# 18_I2S.net
KiCad netlist of a schematic drawn in Altium Designer
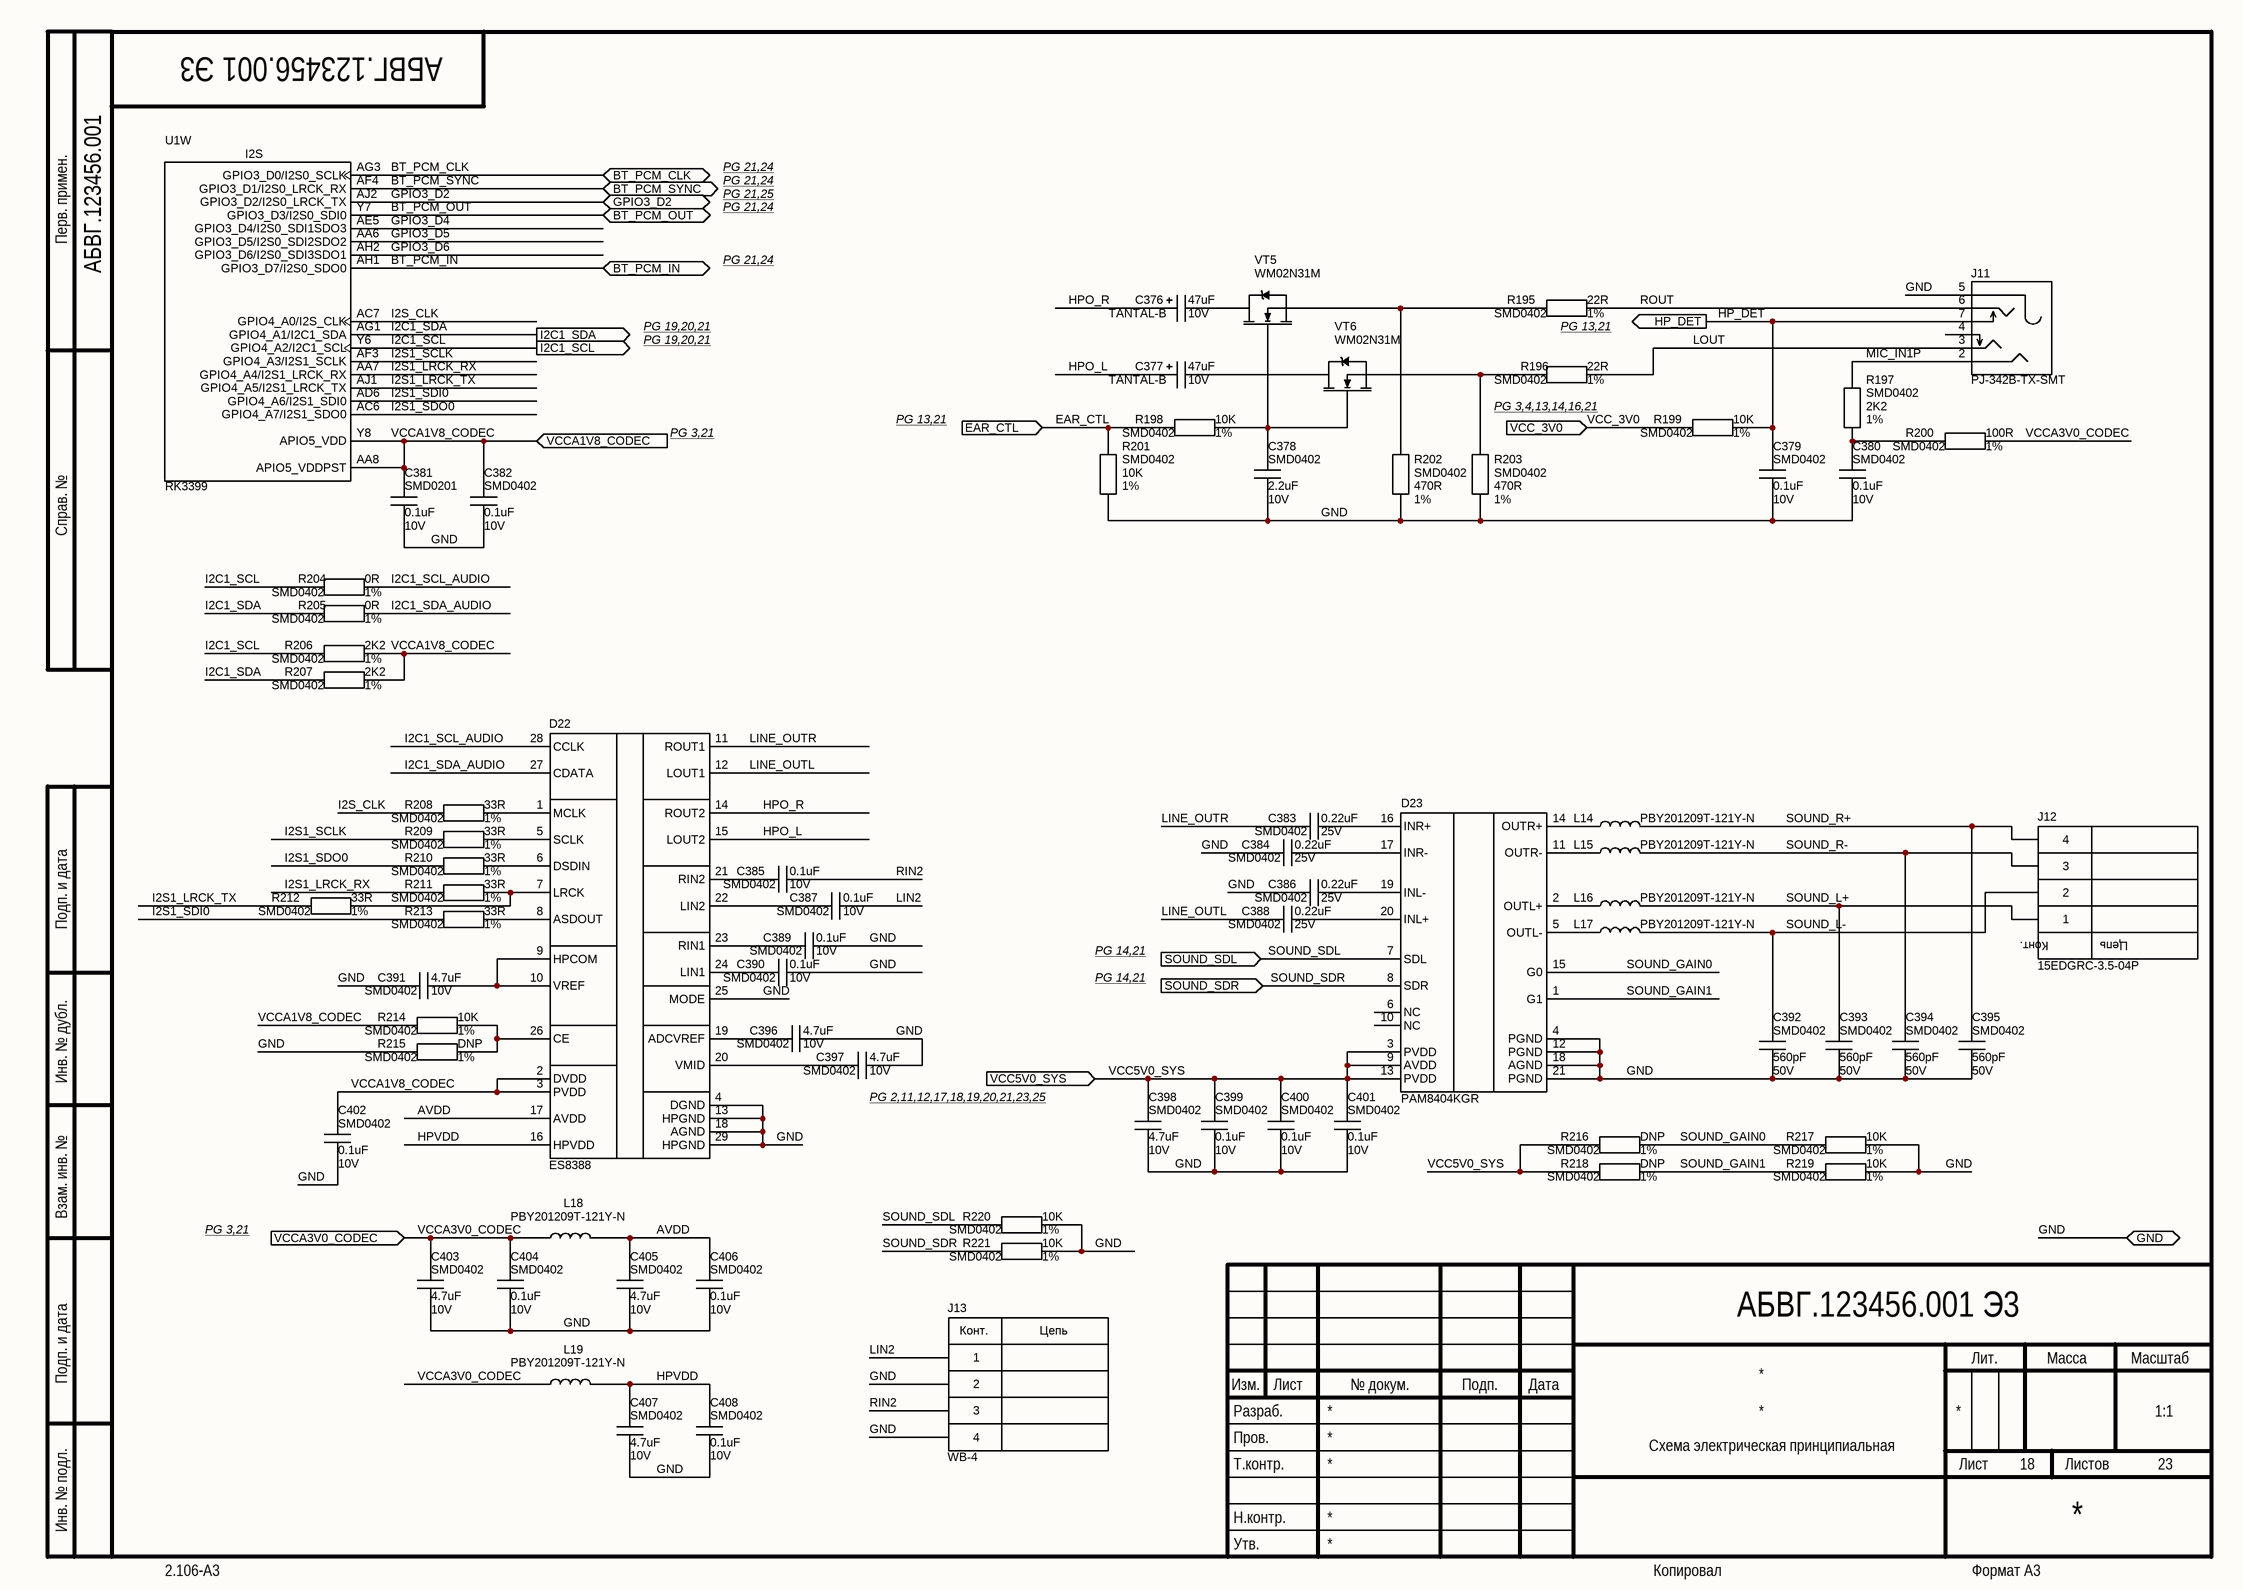
[diagram p0: 18 I2S.SchDoc]

(export (version "E")
  (design (tool "Eeschema 10.0.6"))
  (components
    (comp (ref "C376")
      (value "47uF")
      (footprint "TANTAL-B")
      (fields
        (field (name "PARTNUMBER") "CA45L-B010K476TE500")
        (field (name "TOLERANCE") "20%")
        (field (name "PACKAGE") "TANTAL-B")
        (field (name "VOLTAGE") "10V")
      )
      (libsource (lib "Didur_SchLib_1") (part "Tantal"))
    )
    (comp (ref "C377")
      (value "47uF")
      (footprint "TANTAL-B")
      (fields
        (field (name "PARTNUMBER") "CA45L-B010K476TE500")
        (field (name "TOLERANCE") "20%")
        (field (name "PACKAGE") "TANTAL-B")
        (field (name "VOLTAGE") "10V")
      )
      (libsource (lib "Didur_SchLib_1") (part "Tantal"))
    )
    (comp (ref "C378")
      (value "2.2uF")
      (footprint "Didur_PcbLib_1:CAP_SMD_0402")
      (fields
        (field (name "PACKAGE") "SMD0402")
        (field (name "PARTNUMBER") "CC0402KRX5R6BB225")
        (field (name "VOLTAGE") "10V")
      )
      (libsource (lib "Didur_SchLib_1") (part "Ceramic_Cap"))
    )
    (comp (ref "C379")
      (value "0.1uF")
      (footprint "Didur_PcbLib_1:CAP_SMD_0402")
      (fields
        (field (name "PACKAGE") "SMD0402")
        (field (name "PARTNUMBER") "CC0402KRX5R6BB104")
        (field (name "VOLTAGE") "10V")
      )
      (libsource (lib "Didur_SchLib_1") (part "Ceramic_Cap"))
    )
    (comp (ref "C380")
      (value "0.1uF")
      (footprint "Didur_PcbLib_1:CAP_SMD_0402")
      (fields
        (field (name "PACKAGE") "SMD0402")
        (field (name "PARTNUMBER") "CC0402KRX5R6BB104")
        (field (name "VOLTAGE") "10V")
      )
      (libsource (lib "Didur_SchLib_1") (part "Ceramic_Cap"))
    )
    (comp (ref "C381")
      (value "0.1uF")
      (footprint "Didur_PcbLib_1:CAP_SMD_0201")
      (fields
        (field (name "PACKAGE") "SMD0201")
        (field (name "PARTNUMBER") "CC0201KRX5R6BB104")
        (field (name "VOLTAGE") "10V")
      )
      (libsource (lib "Didur_SchLib_1") (part "Ceramic_Cap"))
    )
    (comp (ref "C382")
      (value "0.1uF")
      (footprint "Didur_PcbLib_1:CAP_SMD_0402")
      (fields
        (field (name "PACKAGE") "SMD0402")
        (field (name "PARTNUMBER") "CC0402KRX5R6BB104")
        (field (name "VOLTAGE") "10V")
      )
      (libsource (lib "Didur_SchLib_1") (part "Ceramic_Cap"))
    )
    (comp (ref "C383")
      (value "0.22uF")
      (footprint "Didur_PcbLib_1:CAP_SMD_0402")
      (fields
        (field (name "PACKAGE") "SMD0402")
        (field (name "PARTNUMBER") "CC0402KRX5R8BB224")
        (field (name "VOLTAGE") "25V")
      )
      (libsource (lib "Didur_SchLib_1") (part "Ceramic_Cap"))
    )
    (comp (ref "C384")
      (value "0.22uF")
      (footprint "Didur_PcbLib_1:CAP_SMD_0402")
      (fields
        (field (name "PACKAGE") "SMD0402")
        (field (name "PARTNUMBER") "CC0402KRX5R8BB224")
        (field (name "VOLTAGE") "25V")
      )
      (libsource (lib "Didur_SchLib_1") (part "Ceramic_Cap"))
    )
    (comp (ref "C385")
      (value "0.1uF")
      (footprint "Didur_PcbLib_1:CAP_SMD_0402")
      (fields
        (field (name "PACKAGE") "SMD0402")
        (field (name "PARTNUMBER") "CC0402KRX5R6BB104")
        (field (name "VOLTAGE") "10V")
      )
      (libsource (lib "Didur_SchLib_1") (part "Ceramic_Cap"))
    )
    (comp (ref "C386")
      (value "0.22uF")
      (footprint "Didur_PcbLib_1:CAP_SMD_0402")
      (fields
        (field (name "PACKAGE") "SMD0402")
        (field (name "PARTNUMBER") "CC0402KRX5R8BB224")
        (field (name "VOLTAGE") "25V")
      )
      (libsource (lib "Didur_SchLib_1") (part "Ceramic_Cap"))
    )
    (comp (ref "C387")
      (value "0.1uF")
      (footprint "Didur_PcbLib_1:CAP_SMD_0402")
      (fields
        (field (name "PACKAGE") "SMD0402")
        (field (name "PARTNUMBER") "CC0402KRX5R6BB104")
        (field (name "VOLTAGE") "10V")
      )
      (libsource (lib "Didur_SchLib_1") (part "Ceramic_Cap"))
    )
    (comp (ref "C388")
      (value "0.22uF")
      (footprint "Didur_PcbLib_1:CAP_SMD_0402")
      (fields
        (field (name "PACKAGE") "SMD0402")
        (field (name "PARTNUMBER") "CC0402KRX5R8BB224")
        (field (name "VOLTAGE") "25V")
      )
      (libsource (lib "Didur_SchLib_1") (part "Ceramic_Cap"))
    )
    (comp (ref "C389")
      (value "0.1uF")
      (footprint "Didur_PcbLib_1:CAP_SMD_0402")
      (fields
        (field (name "PACKAGE") "SMD0402")
        (field (name "PARTNUMBER") "CC0402KRX5R6BB104")
        (field (name "VOLTAGE") "10V")
      )
      (libsource (lib "Didur_SchLib_1") (part "Ceramic_Cap"))
    )
    (comp (ref "C390")
      (value "0.1uF")
      (footprint "Didur_PcbLib_1:CAP_SMD_0402")
      (fields
        (field (name "PACKAGE") "SMD0402")
        (field (name "PARTNUMBER") "CC0402KRX5R6BB104")
        (field (name "VOLTAGE") "10V")
      )
      (libsource (lib "Didur_SchLib_1") (part "Ceramic_Cap"))
    )
    (comp (ref "C391")
      (value "4.7uF")
      (footprint "Didur_PcbLib_1:CAP_SMD_0402")
      (fields
        (field (name "PACKAGE") "SMD0402")
        (field (name "PARTNUMBER") "CL05A475KP5NRNC")
        (field (name "VOLTAGE") "10V")
      )
      (libsource (lib "Didur_SchLib_1") (part "Ceramic_Cap"))
    )
    (comp (ref "C392")
      (value "560pF")
      (footprint "Didur_PcbLib_1:CAP_SMD_0402")
      (fields
        (field (name "PACKAGE") "SMD0402")
        (field (name "PARTNUMBER") "CC0402JRX7R9BB561")
        (field (name "VOLTAGE") "50V")
      )
      (libsource (lib "Didur_SchLib_1") (part "Ceramic_Cap"))
    )
    (comp (ref "C393")
      (value "560pF")
      (footprint "Didur_PcbLib_1:CAP_SMD_0402")
      (fields
        (field (name "PACKAGE") "SMD0402")
        (field (name "PARTNUMBER") "CC0402JRX7R9BB561")
        (field (name "VOLTAGE") "50V")
      )
      (libsource (lib "Didur_SchLib_1") (part "Ceramic_Cap"))
    )
    (comp (ref "C394")
      (value "560pF")
      (footprint "Didur_PcbLib_1:CAP_SMD_0402")
      (fields
        (field (name "PACKAGE") "SMD0402")
        (field (name "PARTNUMBER") "CC0402JRX7R9BB561")
        (field (name "VOLTAGE") "50V")
      )
      (libsource (lib "Didur_SchLib_1") (part "Ceramic_Cap"))
    )
    (comp (ref "C395")
      (value "560pF")
      (footprint "Didur_PcbLib_1:CAP_SMD_0402")
      (fields
        (field (name "PACKAGE") "SMD0402")
        (field (name "PARTNUMBER") "CC0402JRX7R9BB561")
        (field (name "VOLTAGE") "50V")
      )
      (libsource (lib "Didur_SchLib_1") (part "Ceramic_Cap"))
    )
    (comp (ref "C396")
      (value "4.7uF")
      (footprint "Didur_PcbLib_1:CAP_SMD_0402")
      (fields
        (field (name "PACKAGE") "SMD0402")
        (field (name "PARTNUMBER") "CL05A475KP5NRNC")
        (field (name "VOLTAGE") "10V")
      )
      (libsource (lib "Didur_SchLib_1") (part "Ceramic_Cap"))
    )
    (comp (ref "C397")
      (value "4.7uF")
      (footprint "Didur_PcbLib_1:CAP_SMD_0402")
      (fields
        (field (name "PACKAGE") "SMD0402")
        (field (name "PARTNUMBER") "CL05A475KP5NRNC")
        (field (name "VOLTAGE") "10V")
      )
      (libsource (lib "Didur_SchLib_1") (part "Ceramic_Cap"))
    )
    (comp (ref "C398")
      (value "4.7uF")
      (footprint "Didur_PcbLib_1:CAP_SMD_0402")
      (fields
        (field (name "PACKAGE") "SMD0402")
        (field (name "PARTNUMBER") "CL05A475KP5NRNC")
        (field (name "VOLTAGE") "10V")
      )
      (libsource (lib "Didur_SchLib_1") (part "Ceramic_Cap"))
    )
    (comp (ref "C399")
      (value "0.1uF")
      (footprint "Didur_PcbLib_1:CAP_SMD_0402")
      (fields
        (field (name "PACKAGE") "SMD0402")
        (field (name "PARTNUMBER") "CC0402KRX5R6BB104")
        (field (name "VOLTAGE") "10V")
      )
      (libsource (lib "Didur_SchLib_1") (part "Ceramic_Cap"))
    )
    (comp (ref "C400")
      (value "0.1uF")
      (footprint "Didur_PcbLib_1:CAP_SMD_0402")
      (fields
        (field (name "PACKAGE") "SMD0402")
        (field (name "PARTNUMBER") "CC0402KRX5R6BB104")
        (field (name "VOLTAGE") "10V")
      )
      (libsource (lib "Didur_SchLib_1") (part "Ceramic_Cap"))
    )
    (comp (ref "C401")
      (value "0.1uF")
      (footprint "Didur_PcbLib_1:CAP_SMD_0402")
      (fields
        (field (name "PACKAGE") "SMD0402")
        (field (name "PARTNUMBER") "CC0402KRX5R6BB104")
        (field (name "VOLTAGE") "10V")
      )
      (libsource (lib "Didur_SchLib_1") (part "Ceramic_Cap"))
    )
    (comp (ref "C402")
      (value "0.1uF")
      (footprint "Didur_PcbLib_1:CAP_SMD_0402")
      (fields
        (field (name "PACKAGE") "SMD0402")
        (field (name "PARTNUMBER") "CC0402KRX5R6BB104")
        (field (name "VOLTAGE") "10V")
      )
      (libsource (lib "Didur_SchLib_1") (part "Ceramic_Cap"))
    )
    (comp (ref "C403")
      (value "4.7uF")
      (footprint "Didur_PcbLib_1:CAP_SMD_0402")
      (fields
        (field (name "PACKAGE") "SMD0402")
        (field (name "PARTNUMBER") "CL05A475KP5NRNC")
        (field (name "VOLTAGE") "10V")
      )
      (libsource (lib "Didur_SchLib_1") (part "Ceramic_Cap"))
    )
    (comp (ref "C404")
      (value "0.1uF")
      (footprint "Didur_PcbLib_1:CAP_SMD_0402")
      (fields
        (field (name "PACKAGE") "SMD0402")
        (field (name "PARTNUMBER") "CC0402KRX5R6BB104")
        (field (name "VOLTAGE") "10V")
      )
      (libsource (lib "Didur_SchLib_1") (part "Ceramic_Cap"))
    )
    (comp (ref "C405")
      (value "4.7uF")
      (footprint "Didur_PcbLib_1:CAP_SMD_0402")
      (fields
        (field (name "PACKAGE") "SMD0402")
        (field (name "PARTNUMBER") "CL05A475KP5NRNC")
        (field (name "VOLTAGE") "10V")
      )
      (libsource (lib "Didur_SchLib_1") (part "Ceramic_Cap"))
    )
    (comp (ref "C406")
      (value "0.1uF")
      (footprint "Didur_PcbLib_1:CAP_SMD_0402")
      (fields
        (field (name "PACKAGE") "SMD0402")
        (field (name "PARTNUMBER") "CC0402KRX5R6BB104")
        (field (name "VOLTAGE") "10V")
      )
      (libsource (lib "Didur_SchLib_1") (part "Ceramic_Cap"))
    )
    (comp (ref "C407")
      (value "4.7uF")
      (footprint "Didur_PcbLib_1:CAP_SMD_0402")
      (fields
        (field (name "PACKAGE") "SMD0402")
        (field (name "PARTNUMBER") "CL05A475KP5NRNC")
        (field (name "VOLTAGE") "10V")
      )
      (libsource (lib "Didur_SchLib_1") (part "Ceramic_Cap"))
    )
    (comp (ref "C408")
      (value "0.1uF")
      (footprint "Didur_PcbLib_1:CAP_SMD_0402")
      (fields
        (field (name "PACKAGE") "SMD0402")
        (field (name "PARTNUMBER") "CC0402KRX5R6BB104")
        (field (name "VOLTAGE") "10V")
      )
      (libsource (lib "Didur_SchLib_1") (part "Ceramic_Cap"))
    )
    (comp (ref "D22")
      (value "ES8388")
      (footprint "Didur_PcbLib_1:QFN-28 4mmx4mm")
      (libsource (lib "Didur_SchLib_1") (part "ES8388"))
    )
    (comp (ref "D23")
      (value "PAM8404KGR")
      (footprint "Didur_PcbLib_1:QFN-20 4mmx4mm")
      (libsource (lib "Didur_SchLib_1") (part "PAM8404KGR"))
    )
    (comp (ref "J11")
      (value "PJ-342B-TX-SMT")
      (footprint "Didur_PcbLib_1:PJ-342B-TX-SMT")
      (libsource (lib "Didur_SchLib_1") (part "PJ-342B-TX-SMT"))
    )
    (comp (ref "J12")
      (value "15EDGRC-3.5-04P")
      (footprint "Didur_PcbLib_1:15EDGRC-3.5-04P")
      (libsource (lib "") (part "CON4_1"))
    )
    (comp (ref "J13")
      (value "WB-4")
      (footprint "Didur_PcbLib_1:WB-4")
      (fields (field (name "PARTNUMBER") "DS1066-04M(MW-4M)"))
      (libsource (lib "Didur_SchLib_1") (part "CON4"))
    )
    (comp (ref "L14")
      (value "PBY201209T-121Y-N")
      (footprint "Didur_PcbLib_1:IND_SMD_0805")
      (fields (field (name "Comment") "Value"))
      (libsource (lib "Didur_SchLib_1") (part "Inductor_smal"))
    )
    (comp (ref "L15")
      (value "PBY201209T-121Y-N")
      (footprint "Didur_PcbLib_1:IND_SMD_0805")
      (fields (field (name "Comment") "Value"))
      (libsource (lib "Didur_SchLib_1") (part "Inductor_smal"))
    )
    (comp (ref "L16")
      (value "PBY201209T-121Y-N")
      (footprint "Didur_PcbLib_1:IND_SMD_0805")
      (fields (field (name "Comment") "Value"))
      (libsource (lib "Didur_SchLib_1") (part "Inductor_smal"))
    )
    (comp (ref "L17")
      (value "PBY201209T-121Y-N")
      (footprint "Didur_PcbLib_1:IND_SMD_0805")
      (fields (field (name "Comment") "Value"))
      (libsource (lib "Didur_SchLib_1") (part "Inductor_smal"))
    )
    (comp (ref "L18")
      (value "PBY201209T-121Y-N")
      (footprint "Didur_PcbLib_1:IND_SMD_0805")
      (fields (field (name "Comment") "Value"))
      (libsource (lib "Didur_SchLib_1") (part "Inductor_smal"))
    )
    (comp (ref "L19")
      (value "PBY201209T-121Y-N")
      (footprint "Didur_PcbLib_1:IND_SMD_0805")
      (fields (field (name "Comment") "Value"))
      (libsource (lib "Didur_SchLib_1") (part "Inductor_smal"))
    )
    (comp (ref "R195")
      (value "22R")
      (footprint "Didur_PcbLib_1:RES_SMD_0402")
      (fields
        (field (name "PACKAGE") "SMD0402")
        (field (name "PARTNUMBER") "RC0402FR-0722RL")
        (field (name "TOLERANCE") "1%")
      )
      (libsource (lib "") (part "Chip_Res_3"))
    )
    (comp (ref "R196")
      (value "22R")
      (footprint "Didur_PcbLib_1:RES_SMD_0402")
      (fields
        (field (name "PACKAGE") "SMD0402")
        (field (name "PARTNUMBER") "RC0402FR-0722RL")
        (field (name "TOLERANCE") "1%")
      )
      (libsource (lib "") (part "Chip_Res_3"))
    )
    (comp (ref "R197")
      (value "2K2")
      (footprint "Didur_PcbLib_1:RES_SMD_0402")
      (fields
        (field (name "PACKAGE") "SMD0402")
        (field (name "PARTNUMBER") "RC0402FR-072K2L")
        (field (name "TOLERANCE") "1%")
      )
      (libsource (lib "Didur_SchLib_1") (part "Chip_Res"))
    )
    (comp (ref "R198")
      (value "10K")
      (footprint "Didur_PcbLib_1:RES_SMD_0402")
      (fields
        (field (name "PACKAGE") "SMD0402")
        (field (name "PARTNUMBER") "RC0402FR-0710KL")
        (field (name "TOLERANCE") "1%")
      )
      (libsource (lib "") (part "Chip_Res_1"))
    )
    (comp (ref "R199")
      (value "10K")
      (footprint "Didur_PcbLib_1:RES_SMD_0402")
      (fields
        (field (name "PACKAGE") "SMD0402")
        (field (name "PARTNUMBER") "RC0402FR-0710KL")
        (field (name "TOLERANCE") "1%")
      )
      (libsource (lib "") (part "Chip_Res_1"))
    )
    (comp (ref "R200")
      (value "100R")
      (footprint "Didur_PcbLib_1:RES_SMD_0402")
      (fields
        (field (name "PACKAGE") "SMD0402")
        (field (name "PARTNUMBER") "RC0402FR-07100RL")
        (field (name "TOLERANCE") "1%")
      )
      (libsource (lib "Didur_SchLib_1") (part "Chip_Res"))
    )
    (comp (ref "R201")
      (value "10K")
      (footprint "Didur_PcbLib_1:RES_SMD_0402")
      (fields
        (field (name "PACKAGE") "SMD0402")
        (field (name "PARTNUMBER") "RC0402FR-0710KL")
        (field (name "TOLERANCE") "1%")
      )
      (libsource (lib "") (part "Chip_Res_3"))
    )
    (comp (ref "R202")
      (value "470R")
      (footprint "Didur_PcbLib_1:RES_SMD_0402")
      (fields
        (field (name "PACKAGE") "SMD0402")
        (field (name "PARTNUMBER") "RC0402FR-07470RL")
        (field (name "TOLERANCE") "1%")
      )
      (libsource (lib "Didur_SchLib_1") (part "Chip_Res"))
    )
    (comp (ref "R203")
      (value "470R")
      (footprint "Didur_PcbLib_1:RES_SMD_0402")
      (fields
        (field (name "PACKAGE") "SMD0402")
        (field (name "PARTNUMBER") "RC0402FR-07470RL")
        (field (name "TOLERANCE") "1%")
      )
      (libsource (lib "Didur_SchLib_1") (part "Chip_Res"))
    )
    (comp (ref "R204")
      (value "0R")
      (footprint "Didur_PcbLib_1:RES_SMD_0402")
      (fields
        (field (name "PACKAGE") "SMD0402")
        (field (name "PARTNUMBER") "RC0402FR-070RL")
        (field (name "TOLERANCE") "1%")
      )
      (libsource (lib "Didur_SchLib_1") (part "Chip_Res"))
    )
    (comp (ref "R205")
      (value "0R")
      (footprint "Didur_PcbLib_1:RES_SMD_0402")
      (fields
        (field (name "PACKAGE") "SMD0402")
        (field (name "PARTNUMBER") "RC0402FR-070RL")
        (field (name "TOLERANCE") "1%")
      )
      (libsource (lib "Didur_SchLib_1") (part "Chip_Res"))
    )
    (comp (ref "R206")
      (value "2K2")
      (footprint "Didur_PcbLib_1:RES_SMD_0402")
      (fields
        (field (name "PACKAGE") "SMD0402")
        (field (name "PARTNUMBER") "RC0402FR-072K2L")
        (field (name "TOLERANCE") "1%")
      )
      (libsource (lib "") (part "Chip_Res_3"))
    )
    (comp (ref "R207")
      (value "2K2")
      (footprint "Didur_PcbLib_1:RES_SMD_0402")
      (fields
        (field (name "PACKAGE") "SMD0402")
        (field (name "PARTNUMBER") "RC0402FR-072K2L")
        (field (name "TOLERANCE") "1%")
      )
      (libsource (lib "") (part "Chip_Res_3"))
    )
    (comp (ref "R208")
      (value "33R")
      (footprint "Didur_PcbLib_1:RES_SMD_0402")
      (fields
        (field (name "PACKAGE") "SMD0402")
        (field (name "PARTNUMBER") "RC0402FR-0733RL")
        (field (name "TOLERANCE") "1%")
      )
      (libsource (lib "") (part "Chip_Res_2"))
    )
    (comp (ref "R209")
      (value "33R")
      (footprint "Didur_PcbLib_1:RES_SMD_0402")
      (fields
        (field (name "PACKAGE") "SMD0402")
        (field (name "PARTNUMBER") "RC0402FR-0733RL")
        (field (name "TOLERANCE") "1%")
      )
      (libsource (lib "") (part "Chip_Res_2"))
    )
    (comp (ref "R210")
      (value "33R")
      (footprint "Didur_PcbLib_1:RES_SMD_0402")
      (fields
        (field (name "PACKAGE") "SMD0402")
        (field (name "PARTNUMBER") "RC0402FR-0733RL")
        (field (name "TOLERANCE") "1%")
      )
      (libsource (lib "") (part "Chip_Res_2"))
    )
    (comp (ref "R211")
      (value "33R")
      (footprint "Didur_PcbLib_1:RES_SMD_0402")
      (fields
        (field (name "PACKAGE") "SMD0402")
        (field (name "PARTNUMBER") "RC0402FR-0733RL")
        (field (name "TOLERANCE") "1%")
      )
      (libsource (lib "") (part "Chip_Res_2"))
    )
    (comp (ref "R212")
      (value "33R")
      (footprint "Didur_PcbLib_1:RES_SMD_0402")
      (fields
        (field (name "PACKAGE") "SMD0402")
        (field (name "PARTNUMBER") "RC0402FR-0733RL")
        (field (name "TOLERANCE") "1%")
      )
      (libsource (lib "") (part "Chip_Res_2"))
    )
    (comp (ref "R213")
      (value "33R")
      (footprint "Didur_PcbLib_1:RES_SMD_0402")
      (fields
        (field (name "PACKAGE") "SMD0402")
        (field (name "PARTNUMBER") "RC0402FR-0733RL")
        (field (name "TOLERANCE") "1%")
      )
      (libsource (lib "") (part "Chip_Res_2"))
    )
    (comp (ref "R214")
      (value "10K")
      (footprint "Didur_PcbLib_1:RES_SMD_0402")
      (fields
        (field (name "PACKAGE") "SMD0402")
        (field (name "PARTNUMBER") "RC0402FR-0710KL")
        (field (name "TOLERANCE") "1%")
      )
      (libsource (lib "") (part "Chip_Res_1"))
    )
    (comp (ref "R215")
      (value "DNP")
      (footprint "Didur_PcbLib_1:RES_SMD_0402")
      (fields
        (field (name "PACKAGE") "SMD0402")
        (field (name "PARTNUMBER") "Do Not Place")
        (field (name "TOLERANCE") "1%")
      )
      (libsource (lib "Didur_SchLib_1") (part "Chip_Res"))
    )
    (comp (ref "R216")
      (value "DNP")
      (footprint "Didur_PcbLib_1:RES_SMD_0402")
      (fields
        (field (name "PACKAGE") "SMD0402")
        (field (name "PARTNUMBER") "Do Not Place")
        (field (name "TOLERANCE") "1%")
      )
      (libsource (lib "Didur_SchLib_1") (part "Chip_Res"))
    )
    (comp (ref "R217")
      (value "10K")
      (footprint "Didur_PcbLib_1:RES_SMD_0402")
      (fields
        (field (name "PACKAGE") "SMD0402")
        (field (name "PARTNUMBER") "RC0402FR-0710KL")
        (field (name "TOLERANCE") "1%")
      )
      (libsource (lib "") (part "Chip_Res_1"))
    )
    (comp (ref "R218")
      (value "DNP")
      (footprint "Didur_PcbLib_1:RES_SMD_0402")
      (fields
        (field (name "PACKAGE") "SMD0402")
        (field (name "PARTNUMBER") "Do Not Place")
        (field (name "TOLERANCE") "1%")
      )
      (libsource (lib "Didur_SchLib_1") (part "Chip_Res"))
    )
    (comp (ref "R219")
      (value "10K")
      (footprint "Didur_PcbLib_1:RES_SMD_0402")
      (fields
        (field (name "PACKAGE") "SMD0402")
        (field (name "PARTNUMBER") "RC0402FR-0710KL")
        (field (name "TOLERANCE") "1%")
      )
      (libsource (lib "") (part "Chip_Res_1"))
    )
    (comp (ref "R220")
      (value "10K")
      (footprint "Didur_PcbLib_1:RES_SMD_0402")
      (fields
        (field (name "PACKAGE") "SMD0402")
        (field (name "PARTNUMBER") "RC0402FR-0710KL")
        (field (name "TOLERANCE") "1%")
      )
      (libsource (lib "") (part "Chip_Res_1"))
    )
    (comp (ref "R221")
      (value "10K")
      (footprint "Didur_PcbLib_1:RES_SMD_0402")
      (fields
        (field (name "PACKAGE") "SMD0402")
        (field (name "PARTNUMBER") "RC0402FR-0710KL")
        (field (name "TOLERANCE") "1%")
      )
      (libsource (lib "") (part "Chip_Res_1"))
    )
    (comp (ref "U1")
      (value "RK3399")
      (footprint "BGA828C65P31X31_2100X2100X161N")
      (fields (field (name "Comment") "RK3399_FF"))
      (libsource (lib "Didur_SchLib_1") (part "RK3399_FF"))
    )
    (comp (ref "VT5")
      (value "WM02N31M")
      (footprint "SOT23")
      (fields (field (name "Comment") "Value"))
      (libsource (lib "Didur_SchLib_1") (part "MOSFET_N"))
    )
    (comp (ref "VT6")
      (value "WM02N31M")
      (footprint "SOT23")
      (fields (field (name "Comment") "Value"))
      (libsource (lib "Didur_SchLib_1") (part "MOSFET_N"))
    )
  )
  (nets
    (net (code "1") (name "/AVDD") (class "Default")
      (node (ref "C405") (pin "2") (pinfunction "2_2") (pintype "power_in"))
      (node (ref "C406") (pin "1") (pinfunction "1_1") (pintype "power_in"))
      (node (ref "D22") (pin "17") (pinfunction "AVDD_17") (pintype "passive"))
      (node (ref "L18") (pin "1") (pinfunction "1_1") (pintype "passive"))
    )
    (net (code "2") (name "/BT_PCM_CLK") (class "Default")
      (node (ref "U1") (pin "AG3") (pinfunction "GPIO3_D0/I2S0_SCLK_AG3") (pintype "passive"))
    )
    (net (code "3") (name "/BT_PCM_IN") (class "Default")
      (node (ref "U1") (pin "AH1") (pinfunction "GPIO3_D7/I2S0_SDO0_AH1") (pintype "passive"))
    )
    (net (code "4") (name "/BT_PCM_OUT") (class "Default")
      (node (ref "U1") (pin "Y7") (pinfunction "GPIO3_D3/I2S0_SDI0_Y7") (pintype "passive"))
    )
    (net (code "5") (name "/BT_PCM_SYNC") (class "Default")
      (node (ref "U1") (pin "AF4") (pinfunction "GPIO3_D1/I2S0_LRCK_RX_AF4") (pintype "passive"))
    )
    (net (code "6") (name "/EAR_CTL") (class "Default")
      (node (ref "R198") (pin "2") (pinfunction "2_2") (pintype "passive"))
      (node (ref "R201") (pin "1") (pinfunction "1_1") (pintype "passive"))
    )
    (net (code "7") (name "/GND") (class "Default")
      (node (ref "C378") (pin "1") (pinfunction "1_1") (pintype "power_in"))
      (node (ref "C379") (pin "2") (pinfunction "2_2") (pintype "power_in"))
      (node (ref "C380") (pin "2") (pinfunction "2_2") (pintype "power_in"))
      (node (ref "C381") (pin "2") (pinfunction "2_2") (pintype "power_in"))
      (node (ref "C382") (pin "2") (pinfunction "2_2") (pintype "power_in"))
      (node (ref "C384") (pin "2") (pinfunction "2_2") (pintype "power_in"))
      (node (ref "C386") (pin "2") (pinfunction "2_2") (pintype "power_in"))
      (node (ref "C389") (pin "2") (pinfunction "2_2") (pintype "power_in"))
      (node (ref "C390") (pin "2") (pinfunction "2_2") (pintype "power_in"))
      (node (ref "C391") (pin "1") (pinfunction "1_1") (pintype "power_in"))
      (node (ref "C392") (pin "2") (pinfunction "2_2") (pintype "power_in"))
      (node (ref "C393") (pin "2") (pinfunction "2_2") (pintype "power_in"))
      (node (ref "C394") (pin "2") (pinfunction "2_2") (pintype "power_in"))
      (node (ref "C395") (pin "2") (pinfunction "2_2") (pintype "power_in"))
      (node (ref "C396") (pin "2") (pinfunction "2_2") (pintype "power_in"))
      (node (ref "C397") (pin "2") (pinfunction "2_2") (pintype "power_in"))
      (node (ref "C398") (pin "1") (pinfunction "1_1") (pintype "power_in"))
      (node (ref "C399") (pin "2") (pinfunction "2_2") (pintype "power_in"))
      (node (ref "C400") (pin "2") (pinfunction "2_2") (pintype "power_in"))
      (node (ref "C401") (pin "2") (pinfunction "2_2") (pintype "power_in"))
      (node (ref "C402") (pin "2") (pinfunction "2_2") (pintype "power_in"))
      (node (ref "C403") (pin "1") (pinfunction "1_1") (pintype "power_in"))
      (node (ref "C404") (pin "2") (pinfunction "2_2") (pintype "power_in"))
      (node (ref "C405") (pin "1") (pinfunction "1_1") (pintype "power_in"))
      (node (ref "C406") (pin "2") (pinfunction "2_2") (pintype "power_in"))
      (node (ref "C407") (pin "1") (pinfunction "1_1") (pintype "power_in"))
      (node (ref "C408") (pin "2") (pinfunction "2_2") (pintype "power_in"))
      (node (ref "D22") (pin "13") (pinfunction "HPGND_13") (pintype "passive"))
      (node (ref "D22") (pin "18") (pinfunction "AGND_18") (pintype "passive"))
      (node (ref "D22") (pin "25") (pinfunction "MODE_25") (pintype "passive"))
      (node (ref "D22") (pin "29") (pinfunction "HPGND_29") (pintype "passive"))
      (node (ref "D22") (pin "4") (pinfunction "DGND_4") (pintype "passive"))
      (node (ref "D23") (pin "12") (pinfunction "PGND_12") (pintype "passive"))
      (node (ref "D23") (pin "18") (pinfunction "AGND_18") (pintype "passive"))
      (node (ref "D23") (pin "21") (pinfunction "PGND_21") (pintype "passive"))
      (node (ref "D23") (pin "4") (pinfunction "PGND_4") (pintype "passive"))
      (node (ref "J11") (pin "5") (pinfunction "5_5") (pintype "passive"))
      (node (ref "J13") (pin "2") (pinfunction "2_2") (pintype "passive"))
      (node (ref "J13") (pin "4") (pinfunction "4_4") (pintype "power_in"))
      (node (ref "R201") (pin "2") (pinfunction "2_2") (pintype "passive"))
      (node (ref "R202") (pin "1") (pinfunction "1_1") (pintype "passive"))
      (node (ref "R203") (pin "1") (pinfunction "1_1") (pintype "passive"))
      (node (ref "R215") (pin "1") (pinfunction "1_1") (pintype "passive"))
      (node (ref "R217") (pin "1") (pinfunction "1_1") (pintype "passive"))
      (node (ref "R219") (pin "1") (pinfunction "1_1") (pintype "passive"))
      (node (ref "R220") (pin "1") (pinfunction "1_1") (pintype "passive"))
      (node (ref "R221") (pin "1") (pinfunction "1_1") (pintype "passive"))
    )
    (net (code "8") (name "/GPIO3_D2") (class "Default")
      (node (ref "U1") (pin "AJ2") (pinfunction "GPIO3_D2/I2S0_LRCK_TX_AJ2") (pintype "passive"))
    )
    (net (code "9") (name "/GPIO3_D4") (class "Default")
      (node (ref "U1") (pin "AE5") (pinfunction "GPIO3_D4/I2S0_SDI1SDO3_AE5") (pintype "passive"))
    )
    (net (code "10") (name "/GPIO3_D5") (class "Default")
      (node (ref "U1") (pin "AA6") (pinfunction "GPIO3_D5/I2S0_SDI2SDO2_AA6") (pintype "passive"))
    )
    (net (code "11") (name "/GPIO3_D6") (class "Default")
      (node (ref "U1") (pin "AH2") (pinfunction "GPIO3_D6/I2S0_SDI3SDO1_AH2") (pintype "passive"))
    )
    (net (code "12") (name "/HPO_L") (class "Default")
      (node (ref "C377") (pin "1") (pinfunction "1_1") (pintype "power_in"))
      (node (ref "D22") (pin "15") (pinfunction "LOUT2_15") (pintype "passive"))
    )
    (net (code "13") (name "/HPO_R") (class "Default")
      (node (ref "C376") (pin "1") (pinfunction "1_1") (pintype "power_in"))
      (node (ref "D22") (pin "14") (pinfunction "ROUT2_14") (pintype "passive"))
    )
    (net (code "14") (name "/HPVDD") (class "Default")
      (node (ref "C407") (pin "2") (pinfunction "2_2") (pintype "power_in"))
      (node (ref "C408") (pin "1") (pinfunction "1_1") (pintype "power_in"))
      (node (ref "D22") (pin "16") (pinfunction "HPVDD_16") (pintype "passive"))
      (node (ref "L19") (pin "1") (pinfunction "1_1") (pintype "passive"))
    )
    (net (code "15") (name "/HP_DET") (class "Default")
      (node (ref "C379") (pin "1") (pinfunction "1_1") (pintype "power_in"))
      (node (ref "J11") (pin "7") (pinfunction "7_7") (pintype "passive"))
      (node (ref "R199") (pin "1") (pinfunction "1_1") (pintype "passive"))
    )
    (net (code "16") (name "/I2C1_SCL") (class "Default")
      (node (ref "R204") (pin "1") (pinfunction "1_1") (pintype "passive"))
      (node (ref "R206") (pin "2") (pinfunction "2_2") (pintype "passive"))
      (node (ref "U1") (pin "Y6") (pinfunction "GPIO4_A2/I2C1_SCL_Y6") (pintype "passive"))
    )
    (net (code "17") (name "/I2C1_SCL_AUDIO") (class "Default")
      (node (ref "D22") (pin "28") (pinfunction "CCLK_28") (pintype "passive"))
      (node (ref "R204") (pin "2") (pinfunction "2_2") (pintype "passive"))
    )
    (net (code "18") (name "/I2C1_SDA") (class "Default")
      (node (ref "R205") (pin "1") (pinfunction "1_1") (pintype "passive"))
      (node (ref "R207") (pin "2") (pinfunction "2_2") (pintype "passive"))
      (node (ref "U1") (pin "AG1") (pinfunction "GPIO4_A1/I2C1_SDA_AG1") (pintype "passive"))
    )
    (net (code "19") (name "/I2C1_SDA_AUDIO") (class "Default")
      (node (ref "D22") (pin "27") (pinfunction "CDATA_27") (pintype "passive"))
      (node (ref "R205") (pin "2") (pinfunction "2_2") (pintype "passive"))
    )
    (net (code "20") (name "/I2S1_LRCK_RX") (class "Default")
      (node (ref "R211") (pin "1") (pinfunction "1_1") (pintype "passive"))
      (node (ref "U1") (pin "AA7") (pinfunction "GPIO4_A4/I2S1_LRCK_RX_AA7") (pintype "passive"))
    )
    (net (code "21") (name "/I2S1_LRCK_TX") (class "Default")
      (node (ref "R212") (pin "1") (pinfunction "1_1") (pintype "passive"))
      (node (ref "U1") (pin "AJ1") (pinfunction "GPIO4_A5/I2S1_LRCK_TX_AJ1") (pintype "passive"))
    )
    (net (code "22") (name "/I2S1_SCLK") (class "Default")
      (node (ref "R209") (pin "1") (pinfunction "1_1") (pintype "passive"))
      (node (ref "U1") (pin "AF3") (pinfunction "GPIO4_A3/I2S1_SCLK_AF3") (pintype "passive"))
    )
    (net (code "23") (name "/I2S1_SDI0") (class "Default")
      (node (ref "R213") (pin "1") (pinfunction "1_1") (pintype "passive"))
      (node (ref "U1") (pin "AD6") (pinfunction "GPIO4_A6/I2S1_SDI0_AD6") (pintype "passive"))
    )
    (net (code "24") (name "/I2S1_SDO0") (class "Default")
      (node (ref "R210") (pin "1") (pinfunction "1_1") (pintype "passive"))
      (node (ref "U1") (pin "AC6") (pinfunction "GPIO4_A7/I2S1_SDO0_AC6") (pintype "passive"))
    )
    (net (code "25") (name "/I2S_CLK") (class "Default")
      (node (ref "R208") (pin "1") (pinfunction "1_1") (pintype "passive"))
      (node (ref "U1") (pin "AC7") (pinfunction "GPIO4_A0/I2S_CLK_AC7") (pintype "passive"))
    )
    (net (code "26") (name "/LIN2") (class "Default")
      (node (ref "C387") (pin "2") (pinfunction "2_2") (pintype "power_in"))
      (node (ref "J13") (pin "1") (pinfunction "1_1") (pintype "passive"))
    )
    (net (code "27") (name "/LINE_OUTL") (class "Default")
      (node (ref "C388") (pin "2") (pinfunction "2_2") (pintype "power_in"))
      (node (ref "D22") (pin "12") (pinfunction "LOUT1_12") (pintype "passive"))
    )
    (net (code "28") (name "/LINE_OUTR") (class "Default")
      (node (ref "C383") (pin "2") (pinfunction "2_2") (pintype "power_in"))
      (node (ref "D22") (pin "11") (pinfunction "ROUT1_11") (pintype "passive"))
    )
    (net (code "29") (name "/LOUT") (class "Default")
      (node (ref "J11") (pin "3") (pinfunction "3_3") (pintype "passive"))
      (node (ref "R196") (pin "1") (pinfunction "1_1") (pintype "passive"))
    )
    (net (code "30") (name "/MIC_IN1P") (class "Default")
      (node (ref "J11") (pin "2") (pinfunction "2_2") (pintype "passive"))
      (node (ref "R197") (pin "2") (pinfunction "2_2") (pintype "passive"))
    )
    (net (code "31") (name "/RIN2") (class "Default")
      (node (ref "C385") (pin "2") (pinfunction "2_2") (pintype "power_in"))
      (node (ref "J13") (pin "3") (pinfunction "3_3") (pintype "power_in"))
    )
    (net (code "32") (name "/ROUT") (class "Default")
      (node (ref "J11") (pin "6") (pinfunction "6_6") (pintype "passive"))
      (node (ref "R195") (pin "1") (pinfunction "1_1") (pintype "passive"))
    )
    (net (code "33") (name "/SOUND_GAIN0") (class "Default")
      (node (ref "D23") (pin "15") (pinfunction "G0_15") (pintype "passive"))
      (node (ref "R216") (pin "2") (pinfunction "2_2") (pintype "passive"))
      (node (ref "R217") (pin "2") (pinfunction "2_2") (pintype "passive"))
    )
    (net (code "34") (name "/SOUND_GAIN1") (class "Default")
      (node (ref "D23") (pin "1") (pinfunction "G1_1") (pintype "passive"))
      (node (ref "R218") (pin "2") (pinfunction "2_2") (pintype "passive"))
      (node (ref "R219") (pin "2") (pinfunction "2_2") (pintype "passive"))
    )
    (net (code "35") (name "/SOUND_L+") (class "Default")
      (node (ref "C393") (pin "1") (pinfunction "1_1") (pintype "power_in"))
      (node (ref "J12") (pin "1") (pinfunction "1_1") (pintype "passive"))
      (node (ref "L16") (pin "1") (pinfunction "1_1") (pintype "passive"))
    )
    (net (code "36") (name "/SOUND_L-") (class "Default")
      (node (ref "C392") (pin "1") (pinfunction "1_1") (pintype "power_in"))
      (node (ref "J12") (pin "2") (pinfunction "2_2") (pintype "passive"))
      (node (ref "L17") (pin "1") (pinfunction "1_1") (pintype "passive"))
    )
    (net (code "37") (name "/SOUND_R+") (class "Default")
      (node (ref "C395") (pin "1") (pinfunction "1_1") (pintype "power_in"))
      (node (ref "J12") (pin "4") (pinfunction "4_4") (pintype "power_in"))
      (node (ref "L14") (pin "1") (pinfunction "1_1") (pintype "passive"))
    )
    (net (code "38") (name "/SOUND_R-") (class "Default")
      (node (ref "C394") (pin "1") (pinfunction "1_1") (pintype "power_in"))
      (node (ref "J12") (pin "3") (pinfunction "3_3") (pintype "power_in"))
      (node (ref "L15") (pin "1") (pinfunction "1_1") (pintype "passive"))
    )
    (net (code "39") (name "/SOUND_SDL") (class "Default")
      (node (ref "D23") (pin "7") (pinfunction "SDL_7") (pintype "passive"))
      (node (ref "R220") (pin "2") (pinfunction "2_2") (pintype "passive"))
    )
    (net (code "40") (name "/SOUND_SDR") (class "Default")
      (node (ref "D23") (pin "8") (pinfunction "SDR_8") (pintype "passive"))
      (node (ref "R221") (pin "2") (pinfunction "2_2") (pintype "passive"))
    )
    (net (code "41") (name "/VCC5V0_SYS") (class "Default")
      (node (ref "C398") (pin "2") (pinfunction "2_2") (pintype "power_in"))
      (node (ref "C399") (pin "1") (pinfunction "1_1") (pintype "power_in"))
      (node (ref "C400") (pin "1") (pinfunction "1_1") (pintype "power_in"))
      (node (ref "C401") (pin "1") (pinfunction "1_1") (pintype "power_in"))
      (node (ref "D23") (pin "13") (pinfunction "PVDD_13") (pintype "passive"))
      (node (ref "D23") (pin "3") (pinfunction "PVDD_3") (pintype "passive"))
      (node (ref "D23") (pin "9") (pinfunction "AVDD_9") (pintype "passive"))
      (node (ref "R216") (pin "1") (pinfunction "1_1") (pintype "passive"))
      (node (ref "R218") (pin "1") (pinfunction "1_1") (pintype "passive"))
    )
    (net (code "42") (name "/VCCA1V8_CODEC") (class "Default")
      (node (ref "C381") (pin "1") (pinfunction "1_1") (pintype "power_in"))
      (node (ref "C382") (pin "1") (pinfunction "1_1") (pintype "power_in"))
      (node (ref "C402") (pin "1") (pinfunction "1_1") (pintype "power_in"))
      (node (ref "D22") (pin "2") (pinfunction "DVDD_2") (pintype "passive"))
      (node (ref "D22") (pin "3") (pinfunction "PVDD_3") (pintype "passive"))
      (node (ref "R206") (pin "1") (pinfunction "1_1") (pintype "passive"))
      (node (ref "R207") (pin "1") (pinfunction "1_1") (pintype "passive"))
      (node (ref "R214") (pin "2") (pinfunction "2_2") (pintype "passive"))
      (node (ref "U1") (pin "AA8") (pinfunction "APIO5_VDDPST_AA8") (pintype "passive"))
      (node (ref "U1") (pin "Y8") (pinfunction "APIO5_VDD_Y8") (pintype "passive"))
    )
    (net (code "43") (name "/VCCA3V0_CODEC") (class "Default")
      (node (ref "C403") (pin "2") (pinfunction "2_2") (pintype "power_in"))
      (node (ref "C404") (pin "1") (pinfunction "1_1") (pintype "power_in"))
      (node (ref "L18") (pin "2") (pinfunction "2_2") (pintype "passive"))
      (node (ref "L19") (pin "2") (pinfunction "2_2") (pintype "passive"))
      (node (ref "R200") (pin "2") (pinfunction "2_2") (pintype "passive"))
    )
    (net (code "44") (name "/VCC_3V0") (class "Default")
      (node (ref "R199") (pin "2") (pinfunction "2_2") (pintype "passive"))
    )
    (net (code "45") (name "Net-(C380-Pad1)") (class "Default")
      (node (ref "C380") (pin "1") (pinfunction "1_1") (pintype "power_in"))
      (node (ref "R197") (pin "1") (pinfunction "1_1") (pintype "passive"))
      (node (ref "R200") (pin "1") (pinfunction "1_1") (pintype "passive"))
    )
    (net (code "46") (name "Net-(D22-ADCVREF)") (class "Default")
      (node (ref "C396") (pin "1") (pinfunction "1_1") (pintype "power_in"))
      (node (ref "D22") (pin "19") (pinfunction "ADCVREF_19") (pintype "passive"))
    )
    (net (code "47") (name "Net-(D22-ASDOUT)") (class "Default")
      (node (ref "D22") (pin "8") (pinfunction "ASDOUT_8") (pintype "passive"))
      (node (ref "R213") (pin "2") (pinfunction "2_2") (pintype "passive"))
    )
    (net (code "48") (name "Net-(D22-CE)") (class "Default")
      (node (ref "D22") (pin "26") (pinfunction "CE_26") (pintype "passive"))
      (node (ref "R214") (pin "1") (pinfunction "1_1") (pintype "passive"))
      (node (ref "R215") (pin "2") (pinfunction "2_2") (pintype "passive"))
    )
    (net (code "49") (name "Net-(D22-DSDIN)") (class "Default")
      (node (ref "D22") (pin "6") (pinfunction "DSDIN_6") (pintype "passive"))
      (node (ref "R210") (pin "2") (pinfunction "2_2") (pintype "passive"))
    )
    (net (code "50") (name "Net-(D22-HPCOM)") (class "Default")
      (node (ref "C391") (pin "2") (pinfunction "2_2") (pintype "power_in"))
      (node (ref "D22") (pin "10") (pinfunction "VREF_10") (pintype "passive"))
      (node (ref "D22") (pin "9") (pinfunction "HPCOM_9") (pintype "passive"))
    )
    (net (code "51") (name "Net-(D22-LIN1)") (class "Default")
      (node (ref "C390") (pin "1") (pinfunction "1_1") (pintype "power_in"))
      (node (ref "D22") (pin "24") (pinfunction "LIN1_24") (pintype "passive"))
    )
    (net (code "52") (name "Net-(D22-LIN2)") (class "Default")
      (node (ref "C387") (pin "1") (pinfunction "1_1") (pintype "power_in"))
      (node (ref "D22") (pin "22") (pinfunction "LIN2_22") (pintype "passive"))
    )
    (net (code "53") (name "Net-(D22-LRCK)") (class "Default")
      (node (ref "D22") (pin "7") (pinfunction "LRCK_7") (pintype "passive"))
      (node (ref "R211") (pin "2") (pinfunction "2_2") (pintype "passive"))
      (node (ref "R212") (pin "2") (pinfunction "2_2") (pintype "passive"))
    )
    (net (code "54") (name "Net-(D22-MCLK)") (class "Default")
      (node (ref "D22") (pin "1") (pinfunction "MCLK_1") (pintype "passive"))
      (node (ref "R208") (pin "2") (pinfunction "2_2") (pintype "passive"))
    )
    (net (code "55") (name "Net-(D22-RIN1)") (class "Default")
      (node (ref "C389") (pin "1") (pinfunction "1_1") (pintype "power_in"))
      (node (ref "D22") (pin "23") (pinfunction "RIN1_23") (pintype "passive"))
    )
    (net (code "56") (name "Net-(D22-RIN2)") (class "Default")
      (node (ref "C385") (pin "1") (pinfunction "1_1") (pintype "power_in"))
      (node (ref "D22") (pin "21") (pinfunction "RIN2_21") (pintype "passive"))
    )
    (net (code "57") (name "Net-(D22-SCLK)") (class "Default")
      (node (ref "D22") (pin "5") (pinfunction "SCLK_5") (pintype "passive"))
      (node (ref "R209") (pin "2") (pinfunction "2_2") (pintype "passive"))
    )
    (net (code "58") (name "Net-(D22-VMID)") (class "Default")
      (node (ref "C397") (pin "1") (pinfunction "1_1") (pintype "power_in"))
      (node (ref "D22") (pin "20") (pinfunction "VMID_20") (pintype "passive"))
    )
    (net (code "59") (name "Net-(D23-INL+)") (class "Default")
      (node (ref "C388") (pin "1") (pinfunction "1_1") (pintype "power_in"))
      (node (ref "D23") (pin "20") (pinfunction "INL+_20") (pintype "passive"))
    )
    (net (code "60") (name "Net-(D23-INL-)") (class "Default")
      (node (ref "C386") (pin "1") (pinfunction "1_1") (pintype "power_in"))
      (node (ref "D23") (pin "19") (pinfunction "INL-_19") (pintype "passive"))
    )
    (net (code "61") (name "Net-(D23-INR+)") (class "Default")
      (node (ref "C383") (pin "1") (pinfunction "1_1") (pintype "power_in"))
      (node (ref "D23") (pin "16") (pinfunction "INR+_16") (pintype "passive"))
    )
    (net (code "62") (name "Net-(D23-INR-)") (class "Default")
      (node (ref "C384") (pin "1") (pinfunction "1_1") (pintype "power_in"))
      (node (ref "D23") (pin "17") (pinfunction "INR-_17") (pintype "passive"))
    )
    (net (code "63") (name "Net-(D23-OUTL+)") (class "Default")
      (node (ref "D23") (pin "2") (pinfunction "OUTL+_2") (pintype "passive"))
      (node (ref "L16") (pin "2") (pinfunction "2_2") (pintype "passive"))
    )
    (net (code "64") (name "Net-(D23-OUTL-)") (class "Default")
      (node (ref "D23") (pin "5") (pinfunction "OUTL-_5") (pintype "passive"))
      (node (ref "L17") (pin "2") (pinfunction "2_2") (pintype "passive"))
    )
    (net (code "65") (name "Net-(D23-OUTR+)") (class "Default")
      (node (ref "D23") (pin "14") (pinfunction "OUTR+_14") (pintype "passive"))
      (node (ref "L14") (pin "2") (pinfunction "2_2") (pintype "passive"))
    )
    (net (code "66") (name "Net-(D23-OUTR-)") (class "Default")
      (node (ref "D23") (pin "11") (pinfunction "OUTR-_11") (pintype "passive"))
      (node (ref "L15") (pin "2") (pinfunction "2_2") (pintype "passive"))
    )
    (net (code "67") (name "Net-(VT5-D)") (class "Default")
      (node (ref "C376") (pin "2") (pinfunction "2_2") (pintype "power_in"))
      (node (ref "VT5") (pin "3") (pinfunction "D_3") (pintype "passive"))
    )
    (net (code "68") (name "Net-(VT5-G)") (class "Default")
      (node (ref "C378") (pin "2") (pinfunction "2_2") (pintype "power_in"))
      (node (ref "R198") (pin "1") (pinfunction "1_1") (pintype "passive"))
      (node (ref "VT5") (pin "1") (pinfunction "G_1") (pintype "passive"))
      (node (ref "VT6") (pin "1") (pinfunction "G_1") (pintype "passive"))
    )
    (net (code "69") (name "Net-(VT5-S)") (class "Default")
      (node (ref "R195") (pin "2") (pinfunction "2_2") (pintype "passive"))
      (node (ref "R202") (pin "2") (pinfunction "2_2") (pintype "passive"))
      (node (ref "VT5") (pin "2") (pinfunction "S_2") (pintype "passive"))
    )
    (net (code "70") (name "Net-(VT6-D)") (class "Default")
      (node (ref "C377") (pin "2") (pinfunction "2_2") (pintype "power_in"))
      (node (ref "VT6") (pin "3") (pinfunction "D_3") (pintype "passive"))
    )
    (net (code "71") (name "Net-(VT6-S)") (class "Default")
      (node (ref "R196") (pin "2") (pinfunction "2_2") (pintype "passive"))
      (node (ref "R203") (pin "2") (pinfunction "2_2") (pintype "passive"))
      (node (ref "VT6") (pin "2") (pinfunction "S_2") (pintype "passive"))
    )
    (net (code "72") (name "unconnected-(D23-NC-Pad6)") (class "Default")
      (node (ref "D23") (pin "6") (pinfunction "NC_6") (pintype "passive"))
    )
    (net (code "73") (name "unconnected-(D23-NC-Pad10)") (class "Default")
      (node (ref "D23") (pin "10") (pinfunction "NC_10") (pintype "passive"))
    )
    (net (code "74") (name "unconnected-(J11-Pad4)") (class "Default")
      (node (ref "J11") (pin "4") (pinfunction "4_4") (pintype "passive"))
    )
  )
)
